# Processor.net
KiCad netlist of a schematic drawn in Altium Designer
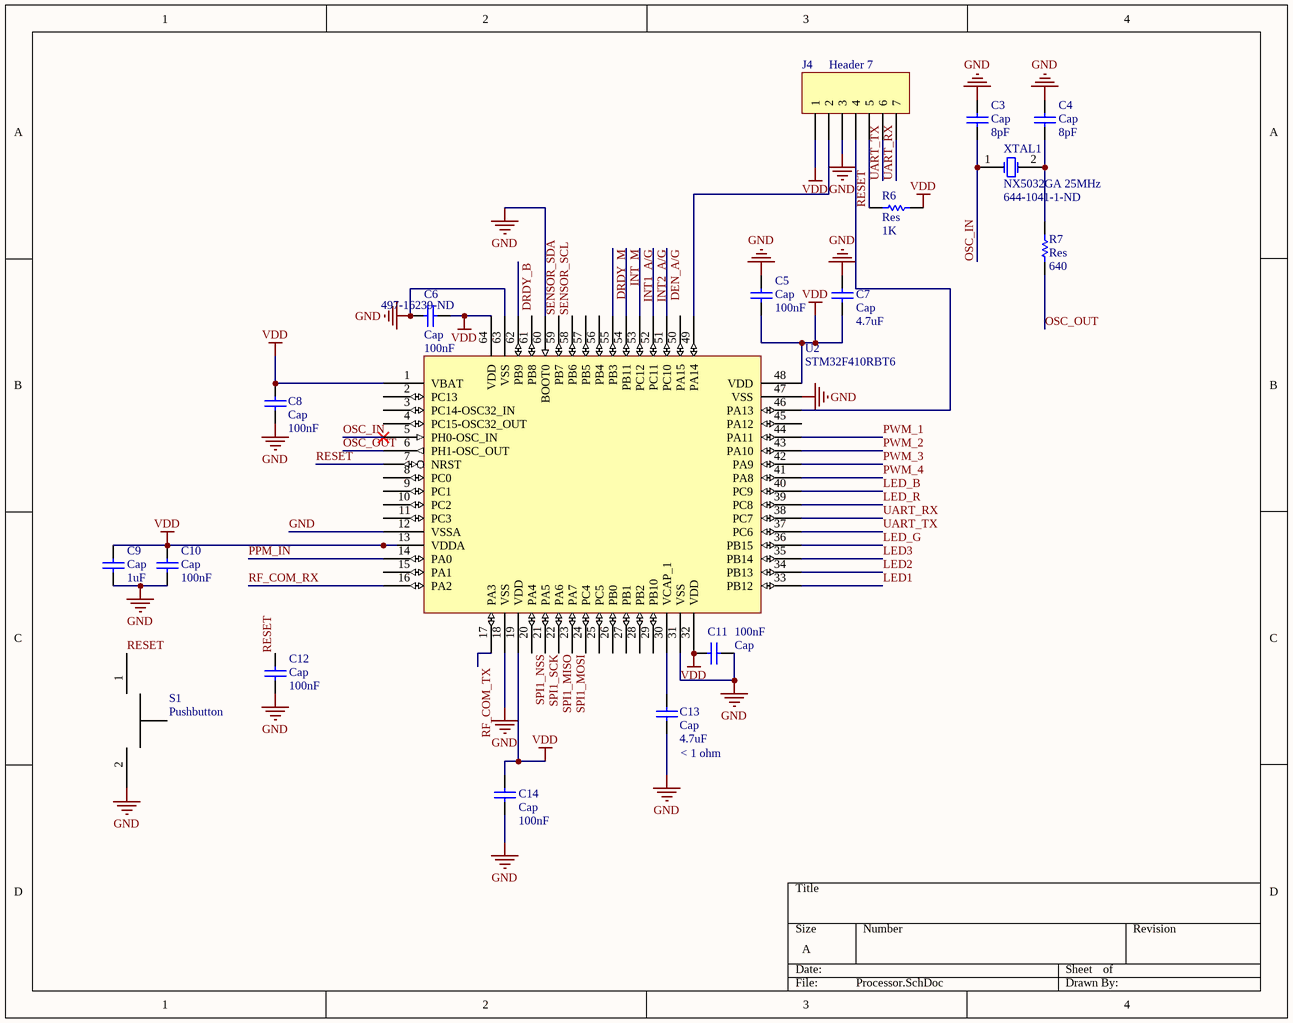
[diagram p0: Processor.SchDoc]

(export (version "E")
  (design (tool "Eeschema 10.0.6"))
  (components
    (comp (ref "C3")
      (value "Cap")
      (footprint "C0805")
      (description "Capacitor")
      (fields (field (name "ALTIUM_VALUE") "8pF") (field (name "PUBLISHER") "Altium Limited"))
      (libsource (lib "Capacitors") (part "Cap"))
    )
    (comp (ref "C4")
      (value "Cap")
      (footprint "C0805")
      (description "Capacitor")
      (fields (field (name "ALTIUM_VALUE") "8pF") (field (name "PUBLISHER") "Altium Limited"))
      (libsource (lib "Capacitors") (part "Cap"))
    )
    (comp (ref "C5")
      (value "Cap")
      (footprint "C0805")
      (description "Capacitor")
      (fields (field (name "ALTIUM_VALUE") "100nF") (field (name "PUBLISHER") "Altium Limited"))
      (libsource (lib "Capacitors") (part "Cap"))
    )
    (comp (ref "C6")
      (value "Cap")
      (footprint "C0805")
      (description "Capacitor")
      (fields (field (name "ALTIUM_VALUE") "100nF") (field (name "PUBLISHER") "Altium Limited"))
      (libsource (lib "Capacitors") (part "Cap"))
    )
    (comp (ref "C7")
      (value "Cap")
      (footprint "C0805")
      (description "Capacitor")
      (fields (field (name "ALTIUM_VALUE") "4.7uF") (field (name "PUBLISHER") "Altium Limited"))
      (libsource (lib "Capacitors") (part "Cap"))
    )
    (comp (ref "C8")
      (value "Cap")
      (footprint "C0805")
      (description "Capacitor")
      (fields (field (name "ALTIUM_VALUE") "100nF") (field (name "PUBLISHER") "Altium Limited"))
      (libsource (lib "Capacitors") (part "Cap"))
    )
    (comp (ref "C9")
      (value "Cap")
      (footprint "C0805")
      (description "Capacitor")
      (fields (field (name "ALTIUM_VALUE") "1uF") (field (name "PUBLISHER") "Altium Limited"))
      (libsource (lib "Capacitors") (part "Cap"))
    )
    (comp (ref "C10")
      (value "Cap")
      (footprint "C0805")
      (description "Capacitor")
      (fields (field (name "ALTIUM_VALUE") "100nF") (field (name "PUBLISHER") "Altium Limited"))
      (libsource (lib "Capacitors") (part "Cap"))
    )
    (comp (ref "C11")
      (value "Cap")
      (footprint "C0805")
      (description "Capacitor")
      (fields (field (name "ALTIUM_VALUE") "100nF") (field (name "PUBLISHER") "Altium Limited"))
      (libsource (lib "Capacitors") (part "Cap"))
    )
    (comp (ref "C12")
      (value "Cap")
      (footprint "C0805")
      (description "Capacitor")
      (fields (field (name "ALTIUM_VALUE") "100nF") (field (name "PUBLISHER") "Altium Limited"))
      (libsource (lib "Capacitors") (part "Cap"))
    )
    (comp (ref "C13")
      (value "Cap")
      (footprint "C0805")
      (description "Capacitor")
      (fields
        (field (name "ALTIUM_VALUE") "4.7uF")
        (field (name "ESR") "< 1 ohm")
        (field (name "PUBLISHER") "Altium Limited")
      )
      (libsource (lib "Capacitors") (part "Cap"))
    )
    (comp (ref "C14")
      (value "Cap")
      (footprint "C0805")
      (description "Capacitor")
      (fields (field (name "ALTIUM_VALUE") "100nF") (field (name "PUBLISHER") "Altium Limited"))
      (libsource (lib "Capacitors") (part "Cap"))
    )
    (comp (ref "J4")
      (value "Header 7")
      (footprint "HDR1X7")
      (description "Header, 7-Pin")
      (fields (field (name "PUBLISHER") "Altium Limited"))
      (libsource (lib "Connectors and Headers") (part "Header 7"))
    )
    (comp (ref "R6")
      (value "Res")
      (footprint "3216[1206]")
      (description "Surface Mount Resistor")
      (fields (field (name "ALTIUM_VALUE") "1K") (field (name "PUBLISHER") "Altium Limited"))
      (libsource (lib "Resistors") (part "Res"))
    )
    (comp (ref "R7")
      (value "Res")
      (footprint "3216[1206]")
      (description "Surface Mount Resistor")
      (fields (field (name "ALTIUM_VALUE") "640") (field (name "PUBLISHER") "Altium Limited"))
      (libsource (lib "Resistors") (part "Res"))
    )
    (comp (ref "S1")
      (value "Pushbutton")
      (footprint "TactileSwitch")
      (libsource (lib "FC") (part "Pushbutton"))
    )
    (comp (ref "U2")
      (value "STM32F410RBT6")
      (footprint "LQFP-64 10x10mm")
      (description "64-LQFP - Pinout Representation")
      (fields
        (field (name "MANUFACTURER") "STMicroelectronics")
        (field (name "SUPPLIER PART NUMBER 1") "497-16239-ND")
      )
      (libsource (lib "FC") (part "STM32F410RB_PINOUT"))
    )
    (comp (ref "XTAL1")
      (value "NX5032GA 25MHz")
      (footprint "NX5032GA")
      (description "NX5032GA")
      (fields
        (field (name "MANUFACTURER") "Nihon Dempa Kogyo (NDK)")
        (field (name "MANUFACTURER PART NUMBER") "NX5032GA-25.000000MHZ-LN-CD-1")
        (field (name "SUPPLIER PART NUMBER 1") "644-1041-1-ND")
      )
      (libsource (lib "FC") (part "NX5032GA"))
    )
  )
  (nets
    (net (code "1") (name "/DEN_A{slash}G") (class "Default")
      (node (ref "U2") (pin "51") (pinfunction "PC10_51") (pintype "bidirectional"))
    )
    (net (code "2") (name "/DRDY_B") (class "Default")
      (node (ref "U2") (pin "62") (pinfunction "PB9_62") (pintype "bidirectional"))
    )
    (net (code "3") (name "/DRDY_M") (class "Default")
      (node (ref "U2") (pin "55") (pinfunction "PB3_55") (pintype "bidirectional"))
    )
    (net (code "4") (name "/INT1_A{slash}G") (class "Default")
      (node (ref "U2") (pin "53") (pinfunction "PC12_53") (pintype "bidirectional"))
    )
    (net (code "5") (name "/INT2_A{slash}G") (class "Default")
      (node (ref "U2") (pin "52") (pinfunction "PC11_52") (pintype "bidirectional"))
    )
    (net (code "6") (name "/INT_M") (class "Default")
      (node (ref "U2") (pin "54") (pinfunction "PB11_54") (pintype "bidirectional"))
    )
    (net (code "7") (name "/LED1") (class "Default")
      (node (ref "U2") (pin "33") (pinfunction "PB12_33") (pintype "bidirectional"))
    )
    (net (code "8") (name "/LED2") (class "Default")
      (node (ref "U2") (pin "34") (pinfunction "PB13_34") (pintype "bidirectional"))
    )
    (net (code "9") (name "/LED3") (class "Default")
      (node (ref "U2") (pin "35") (pinfunction "PB14_35") (pintype "bidirectional"))
    )
    (net (code "10") (name "/LED_B") (class "Default")
      (node (ref "U2") (pin "40") (pinfunction "PC9_40") (pintype "bidirectional"))
    )
    (net (code "11") (name "/LED_G") (class "Default")
      (node (ref "U2") (pin "36") (pinfunction "PB15_36") (pintype "bidirectional"))
    )
    (net (code "12") (name "/LED_R") (class "Default")
      (node (ref "U2") (pin "39") (pinfunction "PC8_39") (pintype "bidirectional"))
    )
    (net (code "13") (name "/OSC_IN") (class "Default")
      (node (ref "C3") (pin "2") (pinfunction "2_2") (pintype "passive"))
      (node (ref "U2") (pin "5") (pinfunction "PH0-OSC_IN_5") (pintype "input"))
      (node (ref "XTAL1") (pin "1") (pinfunction "OSC1_1") (pintype "passive"))
    )
    (net (code "14") (name "/OSC_OUT") (class "Default")
      (node (ref "R7") (pin "1") (pinfunction "1_1") (pintype "passive"))
      (node (ref "U2") (pin "6") (pinfunction "PH1-OSC_OUT_6") (pintype "output"))
    )
    (net (code "15") (name "/PPM_IN") (class "Default")
      (node (ref "U2") (pin "14") (pinfunction "PA0_14") (pintype "bidirectional"))
    )
    (net (code "16") (name "/PWM_1") (class "Default")
      (node (ref "U2") (pin "44") (pinfunction "PA11_44") (pintype "bidirectional"))
    )
    (net (code "17") (name "/PWM_2") (class "Default")
      (node (ref "U2") (pin "43") (pinfunction "PA10_43") (pintype "bidirectional"))
    )
    (net (code "18") (name "/PWM_3") (class "Default")
      (node (ref "U2") (pin "42") (pinfunction "PA9_42") (pintype "bidirectional"))
    )
    (net (code "19") (name "/PWM_4") (class "Default")
      (node (ref "U2") (pin "41") (pinfunction "PA8_41") (pintype "bidirectional"))
    )
    (net (code "20") (name "/RESET") (class "Default")
      (node (ref "C12") (pin "1") (pinfunction "1_1") (pintype "passive"))
      (node (ref "J4") (pin "5") (pinfunction "5_5") (pintype "passive"))
      (node (ref "R6") (pin "1") (pinfunction "1_1") (pintype "passive"))
      (node (ref "S1") (pin "1") (pinfunction "1_1") (pintype "power_in"))
      (node (ref "U2") (pin "7") (pinfunction "NRST_7") (pintype "bidirectional"))
    )
    (net (code "21") (name "/RF_COM_RX") (class "Default")
      (node (ref "U2") (pin "16") (pinfunction "PA2_16") (pintype "bidirectional"))
    )
    (net (code "22") (name "/RF_COM_TX") (class "Default")
      (node (ref "U2") (pin "17") (pinfunction "PA3_17") (pintype "bidirectional"))
    )
    (net (code "23") (name "/SENSOR_SCL") (class "Default")
      (node (ref "U2") (pin "58") (pinfunction "PB6_58") (pintype "bidirectional"))
    )
    (net (code "24") (name "/SENSOR_SDA") (class "Default")
      (node (ref "U2") (pin "59") (pinfunction "PB7_59") (pintype "bidirectional"))
    )
    (net (code "25") (name "/SPI1_MISO") (class "Default")
      (node (ref "U2") (pin "22") (pinfunction "PA6_22") (pintype "bidirectional"))
    )
    (net (code "26") (name "/SPI1_MOSI") (class "Default")
      (node (ref "U2") (pin "23") (pinfunction "PA7_23") (pintype "bidirectional"))
    )
    (net (code "27") (name "/SPI1_NSS") (class "Default")
      (node (ref "U2") (pin "20") (pinfunction "PA4_20") (pintype "bidirectional"))
    )
    (net (code "28") (name "/SPI1_SCK") (class "Default")
      (node (ref "U2") (pin "21") (pinfunction "PA5_21") (pintype "bidirectional"))
    )
    (net (code "29") (name "/UART_RX") (class "Default")
      (node (ref "J4") (pin "7") (pinfunction "7_7") (pintype "passive"))
      (node (ref "U2") (pin "38") (pinfunction "PC7_38") (pintype "bidirectional"))
    )
    (net (code "30") (name "/UART_TX") (class "Default")
      (node (ref "J4") (pin "6") (pinfunction "6_6") (pintype "passive"))
      (node (ref "U2") (pin "37") (pinfunction "PC6_37") (pintype "bidirectional"))
    )
    (net (code "31") (name "GND") (class "Default")
      (node (ref "C10") (pin "2") (pinfunction "2_2") (pintype "passive"))
      (node (ref "C11") (pin "2") (pinfunction "2_2") (pintype "passive"))
      (node (ref "C12") (pin "2") (pinfunction "2_2") (pintype "passive"))
      (node (ref "C13") (pin "1") (pinfunction "1_1") (pintype "passive"))
      (node (ref "C14") (pin "1") (pinfunction "1_1") (pintype "passive"))
      (node (ref "C3") (pin "1") (pinfunction "1_1") (pintype "passive"))
      (node (ref "C4") (pin "1") (pinfunction "1_1") (pintype "passive"))
      (node (ref "C5") (pin "2") (pinfunction "2_2") (pintype "passive"))
      (node (ref "C6") (pin "1") (pinfunction "1_1") (pintype "passive"))
      (node (ref "C7") (pin "2") (pinfunction "2_2") (pintype "passive"))
      (node (ref "C8") (pin "2") (pinfunction "2_2") (pintype "passive"))
      (node (ref "C9") (pin "2") (pinfunction "2_2") (pintype "passive"))
      (node (ref "J4") (pin "3") (pinfunction "3_3") (pintype "passive"))
      (node (ref "S1") (pin "2") (pinfunction "2_2") (pintype "power_in"))
      (node (ref "U2") (pin "12") (pinfunction "VSSA_12") (pintype "power_in"))
      (node (ref "U2") (pin "18") (pinfunction "VSS_18") (pintype "power_in"))
      (node (ref "U2") (pin "31") (pinfunction "VSS_31") (pintype "power_in"))
      (node (ref "U2") (pin "47") (pinfunction "VSS_47") (pintype "power_in"))
      (node (ref "U2") (pin "60") (pinfunction "BOOT0_60") (pintype "input"))
      (node (ref "U2") (pin "63") (pinfunction "VSS_63") (pintype "passive"))
    )
    (net (code "32") (name "Net-(U2-PA13)") (class "Default")
      (node (ref "J4") (pin "4") (pinfunction "4_4") (pintype "passive"))
      (node (ref "U2") (pin "46") (pinfunction "PA13_46") (pintype "bidirectional"))
    )
    (net (code "33") (name "Net-(U2-PA14)") (class "Default")
      (node (ref "J4") (pin "2") (pinfunction "2_2") (pintype "passive"))
      (node (ref "U2") (pin "49") (pinfunction "PA14_49") (pintype "bidirectional"))
    )
    (net (code "34") (name "Net-(U2-VCAP_1)") (class "Default")
      (node (ref "C13") (pin "2") (pinfunction "2_2") (pintype "passive"))
      (node (ref "U2") (pin "30") (pinfunction "VCAP_1_30") (pintype "power_in"))
    )
    (net (code "35") (name "Net-(XTAL1-OSC2)") (class "Default")
      (node (ref "C4") (pin "2") (pinfunction "2_2") (pintype "passive"))
      (node (ref "R7") (pin "2") (pinfunction "2_2") (pintype "passive"))
      (node (ref "XTAL1") (pin "2") (pinfunction "OSC2_2") (pintype "passive"))
    )
    (net (code "36") (name "VDD") (class "Default")
      (node (ref "C10") (pin "1") (pinfunction "1_1") (pintype "passive"))
      (node (ref "C11") (pin "1") (pinfunction "1_1") (pintype "passive"))
      (node (ref "C14") (pin "2") (pinfunction "2_2") (pintype "passive"))
      (node (ref "C5") (pin "1") (pinfunction "1_1") (pintype "passive"))
      (node (ref "C6") (pin "2") (pinfunction "2_2") (pintype "passive"))
      (node (ref "C7") (pin "1") (pinfunction "1_1") (pintype "passive"))
      (node (ref "C8") (pin "1") (pinfunction "1_1") (pintype "passive"))
      (node (ref "C9") (pin "1") (pinfunction "1_1") (pintype "passive"))
      (node (ref "J4") (pin "1") (pinfunction "1_1") (pintype "passive"))
      (node (ref "R6") (pin "2") (pinfunction "2_2") (pintype "passive"))
      (node (ref "U2") (pin "1") (pinfunction "VBAT_1") (pintype "power_in"))
      (node (ref "U2") (pin "13") (pinfunction "VDDA_13") (pintype "power_in"))
      (node (ref "U2") (pin "19") (pinfunction "VDD_19") (pintype "power_in"))
      (node (ref "U2") (pin "32") (pinfunction "VDD_32") (pintype "power_in"))
      (node (ref "U2") (pin "48") (pinfunction "VDD_48") (pintype "power_in"))
      (node (ref "U2") (pin "64") (pinfunction "VDD_64") (pintype "passive"))
    )
    (net (code "37") (name "unconnected-(U2-PA1-Pad15)") (class "Default")
      (node (ref "U2") (pin "15") (pinfunction "PA1_15") (pintype "bidirectional"))
    )
    (net (code "38") (name "unconnected-(U2-PA12-Pad45)") (class "Default")
      (node (ref "U2") (pin "45") (pinfunction "PA12_45") (pintype "bidirectional"))
    )
    (net (code "39") (name "unconnected-(U2-PA15-Pad50)") (class "Default")
      (node (ref "U2") (pin "50") (pinfunction "PA15_50") (pintype "bidirectional"))
    )
    (net (code "40") (name "unconnected-(U2-PB0-Pad26)") (class "Default")
      (node (ref "U2") (pin "26") (pinfunction "PB0_26") (pintype "bidirectional"))
    )
    (net (code "41") (name "unconnected-(U2-PB1-Pad27)") (class "Default")
      (node (ref "U2") (pin "27") (pinfunction "PB1_27") (pintype "bidirectional"))
    )
    (net (code "42") (name "unconnected-(U2-PB2-Pad28)") (class "Default")
      (node (ref "U2") (pin "28") (pinfunction "PB2_28") (pintype "bidirectional"))
    )
    (net (code "43") (name "unconnected-(U2-PB4-Pad56)") (class "Default")
      (node (ref "U2") (pin "56") (pinfunction "PB4_56") (pintype "bidirectional"))
    )
    (net (code "44") (name "unconnected-(U2-PB5-Pad57)") (class "Default")
      (node (ref "U2") (pin "57") (pinfunction "PB5_57") (pintype "bidirectional"))
    )
    (net (code "45") (name "unconnected-(U2-PB8-Pad61)") (class "Default")
      (node (ref "U2") (pin "61") (pinfunction "PB8_61") (pintype "bidirectional"))
    )
    (net (code "46") (name "unconnected-(U2-PB10-Pad29)") (class "Default")
      (node (ref "U2") (pin "29") (pinfunction "PB10_29") (pintype "bidirectional"))
    )
    (net (code "47") (name "unconnected-(U2-PC0-Pad8)") (class "Default")
      (node (ref "U2") (pin "8") (pinfunction "PC0_8") (pintype "bidirectional"))
    )
    (net (code "48") (name "unconnected-(U2-PC1-Pad9)") (class "Default")
      (node (ref "U2") (pin "9") (pinfunction "PC1_9") (pintype "bidirectional"))
    )
    (net (code "49") (name "unconnected-(U2-PC2-Pad10)") (class "Default")
      (node (ref "U2") (pin "10") (pinfunction "PC2_10") (pintype "bidirectional"))
    )
    (net (code "50") (name "unconnected-(U2-PC3-Pad11)") (class "Default")
      (node (ref "U2") (pin "11") (pinfunction "PC3_11") (pintype "bidirectional"))
    )
    (net (code "51") (name "unconnected-(U2-PC4-Pad24)") (class "Default")
      (node (ref "U2") (pin "24") (pinfunction "PC4_24") (pintype "bidirectional"))
    )
    (net (code "52") (name "unconnected-(U2-PC5-Pad25)") (class "Default")
      (node (ref "U2") (pin "25") (pinfunction "PC5_25") (pintype "bidirectional"))
    )
    (net (code "53") (name "unconnected-(U2-PC13-Pad2)") (class "Default")
      (node (ref "U2") (pin "2") (pinfunction "PC13_2") (pintype "bidirectional"))
    )
    (net (code "54") (name "unconnected-(U2-PC14-OSC32_IN-Pad3)") (class "Default")
      (node (ref "U2") (pin "3") (pinfunction "PC14-OSC32_IN_3") (pintype "bidirectional"))
    )
    (net (code "55") (name "unconnected-(U2-PC15-OSC32_OUT-Pad4)") (class "Default")
      (node (ref "U2") (pin "4") (pinfunction "PC15-OSC32_OUT_4") (pintype "bidirectional"))
    )
  )
)
